# I2C_Switch.net
KiCad netlist of a schematic drawn in Altium Designer
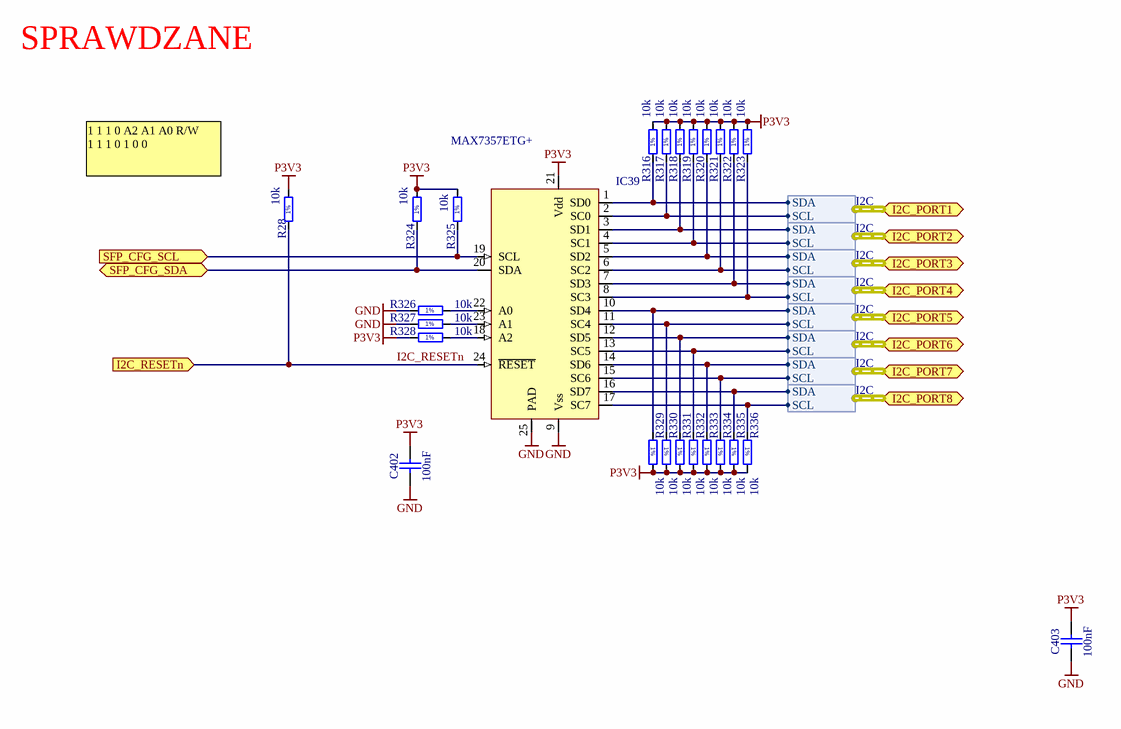
[diagram p0: I2C_Switch.SchDoc]

(export (version "E")
  (design (tool "Eeschema 10.0.6"))
  (components
    (comp (ref "C402")
      (value "100nF")
      (footprint "CAPC0603X33N")
      (description "Non-polarised capacitor")
      (fields
        (field (name "PART NUMBER") "CC0201_100NF_6.3V_10%_X5R")
        (field (name "VOLTAGE") "6.3V")
        (field (name "AUTHOR") "CERN DEM JLC")
      )
      (libsource (lib "Capacitors") (part "Capacitor - non polarized"))
    )
    (comp (ref "C403")
      (value "100nF")
      (footprint "CAPC0603X33N")
      (description "Non-polarised capacitor")
      (fields
        (field (name "PART NUMBER") "CC0201_100NF_6.3V_10%_X5R")
        (field (name "VOLTAGE") "6.3V")
        (field (name "AUTHOR") "CERN DEM JLC")
      )
      (libsource (lib "Capacitors") (part "Capacitor - non polarized"))
    )
    (comp (ref "IC39")
      (value "MAX7357ETG+")
      (footprint "HVQFN24")
      (description "8-channel I2C-bus multiplexer with reset, INT and timeout")
      (libsource (lib "LIBRARY_SCH") (part "IIC_MUX_MAX7357ETG+"))
    )
    (comp (ref "R28")
      (value "10k")
      (footprint "RESC1005X40N")
      (description "Resistor - 1%")
      (fields
        (field (name "PART NUMBER") "R0402_10K_1%_0.0625W_100PPM")
        (field (name "POWER") "0.0625W")
        (field (name "AUTHOR") "CERN DEM JLC")
      )
      (libsource (lib "Resistors") (part "Resistor - 1%"))
    )
    (comp (ref "R316")
      (value "10k")
      (footprint "RESC1005X40N")
      (description "Resistor - 1%")
      (fields
        (field (name "PART NUMBER") "R0402_10K_1%_0.0625W_100PPM")
        (field (name "POWER") "0.0625W")
        (field (name "AUTHOR") "CERN DEM JLC")
      )
      (libsource (lib "Resistors") (part "Resistor - 1%"))
    )
    (comp (ref "R317")
      (value "10k")
      (footprint "RESC1005X40N")
      (description "Resistor - 1%")
      (fields
        (field (name "PART NUMBER") "R0402_10K_1%_0.0625W_100PPM")
        (field (name "POWER") "0.0625W")
        (field (name "AUTHOR") "CERN DEM JLC")
      )
      (libsource (lib "Resistors") (part "Resistor - 1%"))
    )
    (comp (ref "R318")
      (value "10k")
      (footprint "RESC1005X40N")
      (description "Resistor - 1%")
      (fields
        (field (name "PART NUMBER") "R0402_10K_1%_0.0625W_100PPM")
        (field (name "POWER") "0.0625W")
        (field (name "AUTHOR") "CERN DEM JLC")
      )
      (libsource (lib "Resistors") (part "Resistor - 1%"))
    )
    (comp (ref "R319")
      (value "10k")
      (footprint "RESC1005X40N")
      (description "Resistor - 1%")
      (fields
        (field (name "PART NUMBER") "R0402_10K_1%_0.0625W_100PPM")
        (field (name "POWER") "0.0625W")
        (field (name "AUTHOR") "CERN DEM JLC")
      )
      (libsource (lib "Resistors") (part "Resistor - 1%"))
    )
    (comp (ref "R320")
      (value "10k")
      (footprint "RESC1005X40N")
      (description "Resistor - 1%")
      (fields
        (field (name "PART NUMBER") "R0402_10K_1%_0.0625W_100PPM")
        (field (name "POWER") "0.0625W")
        (field (name "AUTHOR") "CERN DEM JLC")
      )
      (libsource (lib "Resistors") (part "Resistor - 1%"))
    )
    (comp (ref "R321")
      (value "10k")
      (footprint "RESC1005X40N")
      (description "Resistor - 1%")
      (fields
        (field (name "PART NUMBER") "R0402_10K_1%_0.0625W_100PPM")
        (field (name "POWER") "0.0625W")
        (field (name "AUTHOR") "CERN DEM JLC")
      )
      (libsource (lib "Resistors") (part "Resistor - 1%"))
    )
    (comp (ref "R322")
      (value "10k")
      (footprint "RESC1005X40N")
      (description "Resistor - 1%")
      (fields
        (field (name "PART NUMBER") "R0402_10K_1%_0.0625W_100PPM")
        (field (name "POWER") "0.0625W")
        (field (name "AUTHOR") "CERN DEM JLC")
      )
      (libsource (lib "Resistors") (part "Resistor - 1%"))
    )
    (comp (ref "R323")
      (value "10k")
      (footprint "RESC1005X40N")
      (description "Resistor - 1%")
      (fields
        (field (name "PART NUMBER") "R0402_10K_1%_0.0625W_100PPM")
        (field (name "POWER") "0.0625W")
        (field (name "AUTHOR") "CERN DEM JLC")
      )
      (libsource (lib "Resistors") (part "Resistor - 1%"))
    )
    (comp (ref "R324")
      (value "10k")
      (footprint "RESC1005X40N")
      (description "Resistor - 1%")
      (fields
        (field (name "PART NUMBER") "R0402_10K_1%_0.0625W_100PPM")
        (field (name "POWER") "0.0625W")
        (field (name "AUTHOR") "CERN DEM JLC")
      )
      (libsource (lib "Resistors") (part "Resistor - 1%"))
    )
    (comp (ref "R325")
      (value "10k")
      (footprint "RESC1005X40N")
      (description "Resistor - 1%")
      (fields
        (field (name "PART NUMBER") "R0402_10K_1%_0.0625W_100PPM")
        (field (name "POWER") "0.0625W")
        (field (name "AUTHOR") "CERN DEM JLC")
      )
      (libsource (lib "Resistors") (part "Resistor - 1%"))
    )
    (comp (ref "R326")
      (value "10k")
      (footprint "RESC1005X40N")
      (description "Resistor - 1%")
      (fields
        (field (name "PART NUMBER") "R0402_10K_1%_0.0625W_100PPM")
        (field (name "POWER") "0.0625W")
        (field (name "AUTHOR") "CERN DEM JLC")
      )
      (libsource (lib "Resistors") (part "Resistor - 1%"))
    )
    (comp (ref "R327")
      (value "10k")
      (footprint "RESC1005X40N")
      (description "Resistor - 1%")
      (fields
        (field (name "PART NUMBER") "R0402_10K_1%_0.0625W_100PPM")
        (field (name "POWER") "0.0625W")
        (field (name "AUTHOR") "CERN DEM JLC")
      )
      (libsource (lib "Resistors") (part "Resistor - 1%"))
    )
    (comp (ref "R328")
      (value "10k")
      (footprint "RESC1005X40N")
      (description "Resistor - 1%")
      (fields
        (field (name "PART NUMBER") "R0402_10K_1%_0.0625W_100PPM")
        (field (name "POWER") "0.0625W")
        (field (name "AUTHOR") "CERN DEM JLC")
      )
      (libsource (lib "Resistors") (part "Resistor - 1%"))
    )
    (comp (ref "R329")
      (value "10k")
      (footprint "RESC1005X40N")
      (description "Resistor - 1%")
      (fields
        (field (name "PART NUMBER") "R0402_10K_1%_0.0625W_100PPM")
        (field (name "POWER") "0.0625W")
        (field (name "AUTHOR") "CERN DEM JLC")
      )
      (libsource (lib "Resistors") (part "Resistor - 1%"))
    )
    (comp (ref "R330")
      (value "10k")
      (footprint "RESC1005X40N")
      (description "Resistor - 1%")
      (fields
        (field (name "PART NUMBER") "R0402_10K_1%_0.0625W_100PPM")
        (field (name "POWER") "0.0625W")
        (field (name "AUTHOR") "CERN DEM JLC")
      )
      (libsource (lib "Resistors") (part "Resistor - 1%"))
    )
    (comp (ref "R331")
      (value "10k")
      (footprint "RESC1005X40N")
      (description "Resistor - 1%")
      (fields
        (field (name "PART NUMBER") "R0402_10K_1%_0.0625W_100PPM")
        (field (name "POWER") "0.0625W")
        (field (name "AUTHOR") "CERN DEM JLC")
      )
      (libsource (lib "Resistors") (part "Resistor - 1%"))
    )
    (comp (ref "R332")
      (value "10k")
      (footprint "RESC1005X40N")
      (description "Resistor - 1%")
      (fields
        (field (name "PART NUMBER") "R0402_10K_1%_0.0625W_100PPM")
        (field (name "POWER") "0.0625W")
        (field (name "AUTHOR") "CERN DEM JLC")
      )
      (libsource (lib "Resistors") (part "Resistor - 1%"))
    )
    (comp (ref "R333")
      (value "10k")
      (footprint "RESC1005X40N")
      (description "Resistor - 1%")
      (fields
        (field (name "PART NUMBER") "R0402_10K_1%_0.0625W_100PPM")
        (field (name "POWER") "0.0625W")
        (field (name "AUTHOR") "CERN DEM JLC")
      )
      (libsource (lib "Resistors") (part "Resistor - 1%"))
    )
    (comp (ref "R334")
      (value "10k")
      (footprint "RESC1005X40N")
      (description "Resistor - 1%")
      (fields
        (field (name "PART NUMBER") "R0402_10K_1%_0.0625W_100PPM")
        (field (name "POWER") "0.0625W")
        (field (name "AUTHOR") "CERN DEM JLC")
      )
      (libsource (lib "Resistors") (part "Resistor - 1%"))
    )
    (comp (ref "R335")
      (value "10k")
      (footprint "RESC1005X40N")
      (description "Resistor - 1%")
      (fields
        (field (name "PART NUMBER") "R0402_10K_1%_0.0625W_100PPM")
        (field (name "POWER") "0.0625W")
        (field (name "AUTHOR") "CERN DEM JLC")
      )
      (libsource (lib "Resistors") (part "Resistor - 1%"))
    )
    (comp (ref "R336")
      (value "10k")
      (footprint "RESC1005X40N")
      (description "Resistor - 1%")
      (fields
        (field (name "PART NUMBER") "R0402_10K_1%_0.0625W_100PPM")
        (field (name "POWER") "0.0625W")
        (field (name "AUTHOR") "CERN DEM JLC")
      )
      (libsource (lib "Resistors") (part "Resistor - 1%"))
    )
  )
  (nets
    (net (code "2") (name "/I2C_RESETn") (class "Default")
      (node (ref "IC39") (pin "24") (pinfunction "~{RESET}_24") (pintype "input"))
      (node (ref "R28") (pin "1") (pinfunction "1_1") (pintype "passive"))
    )
    (net (code "3") (name "/SFP_CFG_SCL") (class "Default")
      (node (ref "IC39") (pin "19") (pinfunction "SCL_19") (pintype "input"))
      (node (ref "R325") (pin "1") (pinfunction "1_1") (pintype "passive"))
    )
    (net (code "4") (name "/SFP_CFG_SDA") (class "Default")
      (node (ref "IC39") (pin "20") (pinfunction "SDA_20") (pintype "bidirectional"))
      (node (ref "R324") (pin "1") (pinfunction "1_1") (pintype "passive"))
    )
    (net (code "6") (name "GND") (class "Default")
      (node (ref "C402") (pin "1") (pinfunction "1_1") (pintype "passive"))
      (node (ref "C403") (pin "1") (pinfunction "1_1") (pintype "passive"))
      (node (ref "IC39") (pin "25") (pinfunction "PAD_25") (pintype "power_in"))
      (node (ref "IC39") (pin "9") (pinfunction "Vss_9") (pintype "power_in"))
      (node (ref "R326") (pin "1") (pinfunction "1_1") (pintype "passive"))
      (node (ref "R327") (pin "1") (pinfunction "1_1") (pintype "passive"))
    )
    (net (code "7") (name "Net-(IC39-A0)") (class "Default")
      (node (ref "IC39") (pin "22") (pinfunction "A0_22") (pintype "input"))
      (node (ref "R326") (pin "2") (pinfunction "2_2") (pintype "passive"))
    )
    (net (code "8") (name "Net-(IC39-A1)") (class "Default")
      (node (ref "IC39") (pin "23") (pinfunction "A1_23") (pintype "input"))
      (node (ref "R327") (pin "2") (pinfunction "2_2") (pintype "passive"))
    )
    (net (code "9") (name "Net-(IC39-A2)") (class "Default")
      (node (ref "IC39") (pin "18") (pinfunction "A2_18") (pintype "input"))
      (node (ref "R328") (pin "2") (pinfunction "2_2") (pintype "passive"))
    )
    (net (code "10") (name "Net-(IC39-SC0)") (class "Default")
      (node (ref "IC39") (pin "2") (pinfunction "SC0_2") (pintype "bidirectional"))
      (node (ref "R317") (pin "1") (pinfunction "1_1") (pintype "passive"))
    )
    (net (code "11") (name "Net-(IC39-SC1)") (class "Default")
      (node (ref "IC39") (pin "4") (pinfunction "SC1_4") (pintype "bidirectional"))
      (node (ref "R319") (pin "1") (pinfunction "1_1") (pintype "passive"))
    )
    (net (code "12") (name "Net-(IC39-SC2)") (class "Default")
      (node (ref "IC39") (pin "6") (pinfunction "SC2_6") (pintype "bidirectional"))
      (node (ref "R321") (pin "1") (pinfunction "1_1") (pintype "passive"))
    )
    (net (code "13") (name "Net-(IC39-SC3)") (class "Default")
      (node (ref "IC39") (pin "8") (pinfunction "SC3_8") (pintype "bidirectional"))
      (node (ref "R323") (pin "1") (pinfunction "1_1") (pintype "passive"))
    )
    (net (code "14") (name "Net-(IC39-SC4)") (class "Default")
      (node (ref "IC39") (pin "11") (pinfunction "SC4_11") (pintype "bidirectional"))
      (node (ref "R330") (pin "1") (pinfunction "1_1") (pintype "passive"))
    )
    (net (code "15") (name "Net-(IC39-SC5)") (class "Default")
      (node (ref "IC39") (pin "13") (pinfunction "SC5_13") (pintype "bidirectional"))
      (node (ref "R332") (pin "1") (pinfunction "1_1") (pintype "passive"))
    )
    (net (code "16") (name "Net-(IC39-SC6)") (class "Default")
      (node (ref "IC39") (pin "15") (pinfunction "SC6_15") (pintype "bidirectional"))
      (node (ref "R334") (pin "1") (pinfunction "1_1") (pintype "passive"))
    )
    (net (code "17") (name "Net-(IC39-SC7)") (class "Default")
      (node (ref "IC39") (pin "17") (pinfunction "SC7_17") (pintype "bidirectional"))
      (node (ref "R336") (pin "1") (pinfunction "1_1") (pintype "passive"))
    )
    (net (code "18") (name "Net-(IC39-SD0)") (class "Default")
      (node (ref "IC39") (pin "1") (pinfunction "SD0_1") (pintype "bidirectional"))
      (node (ref "R316") (pin "1") (pinfunction "1_1") (pintype "passive"))
    )
    (net (code "19") (name "Net-(IC39-SD1)") (class "Default")
      (node (ref "IC39") (pin "3") (pinfunction "SD1_3") (pintype "bidirectional"))
      (node (ref "R318") (pin "1") (pinfunction "1_1") (pintype "passive"))
    )
    (net (code "20") (name "Net-(IC39-SD2)") (class "Default")
      (node (ref "IC39") (pin "5") (pinfunction "SD2_5") (pintype "bidirectional"))
      (node (ref "R320") (pin "1") (pinfunction "1_1") (pintype "passive"))
    )
    (net (code "21") (name "Net-(IC39-SD3)") (class "Default")
      (node (ref "IC39") (pin "7") (pinfunction "SD3_7") (pintype "bidirectional"))
      (node (ref "R322") (pin "1") (pinfunction "1_1") (pintype "passive"))
    )
    (net (code "22") (name "Net-(IC39-SD4)") (class "Default")
      (node (ref "IC39") (pin "10") (pinfunction "SD4_10") (pintype "bidirectional"))
      (node (ref "R329") (pin "1") (pinfunction "1_1") (pintype "passive"))
    )
    (net (code "23") (name "Net-(IC39-SD5)") (class "Default")
      (node (ref "IC39") (pin "12") (pinfunction "SD5_12") (pintype "bidirectional"))
      (node (ref "R331") (pin "1") (pinfunction "1_1") (pintype "passive"))
    )
    (net (code "24") (name "Net-(IC39-SD6)") (class "Default")
      (node (ref "IC39") (pin "14") (pinfunction "SD6_14") (pintype "bidirectional"))
      (node (ref "R333") (pin "1") (pinfunction "1_1") (pintype "passive"))
    )
    (net (code "25") (name "Net-(IC39-SD7)") (class "Default")
      (node (ref "IC39") (pin "16") (pinfunction "SD7_16") (pintype "bidirectional"))
      (node (ref "R335") (pin "1") (pinfunction "1_1") (pintype "passive"))
    )
    (net (code "26") (name "P3V3") (class "Default")
      (node (ref "C402") (pin "2") (pinfunction "2_2") (pintype "passive"))
      (node (ref "C403") (pin "2") (pinfunction "2_2") (pintype "passive"))
      (node (ref "IC39") (pin "21") (pinfunction "Vdd_21") (pintype "power_in"))
      (node (ref "R28") (pin "2") (pinfunction "2_2") (pintype "passive"))
      (node (ref "R316") (pin "2") (pinfunction "2_2") (pintype "passive"))
      (node (ref "R317") (pin "2") (pinfunction "2_2") (pintype "passive"))
      (node (ref "R318") (pin "2") (pinfunction "2_2") (pintype "passive"))
      (node (ref "R319") (pin "2") (pinfunction "2_2") (pintype "passive"))
      (node (ref "R320") (pin "2") (pinfunction "2_2") (pintype "passive"))
      (node (ref "R321") (pin "2") (pinfunction "2_2") (pintype "passive"))
      (node (ref "R322") (pin "2") (pinfunction "2_2") (pintype "passive"))
      (node (ref "R323") (pin "2") (pinfunction "2_2") (pintype "passive"))
      (node (ref "R324") (pin "2") (pinfunction "2_2") (pintype "passive"))
      (node (ref "R325") (pin "2") (pinfunction "2_2") (pintype "passive"))
      (node (ref "R328") (pin "1") (pinfunction "1_1") (pintype "passive"))
      (node (ref "R329") (pin "2") (pinfunction "2_2") (pintype "passive"))
      (node (ref "R330") (pin "2") (pinfunction "2_2") (pintype "passive"))
      (node (ref "R331") (pin "2") (pinfunction "2_2") (pintype "passive"))
      (node (ref "R332") (pin "2") (pinfunction "2_2") (pintype "passive"))
      (node (ref "R333") (pin "2") (pinfunction "2_2") (pintype "passive"))
      (node (ref "R334") (pin "2") (pinfunction "2_2") (pintype "passive"))
      (node (ref "R335") (pin "2") (pinfunction "2_2") (pintype "passive"))
      (node (ref "R336") (pin "2") (pinfunction "2_2") (pintype "passive"))
    )
  )
)
